# POWR0001_BCR_LT1513.net
KiCad netlist of a schematic drawn in Altium Designer
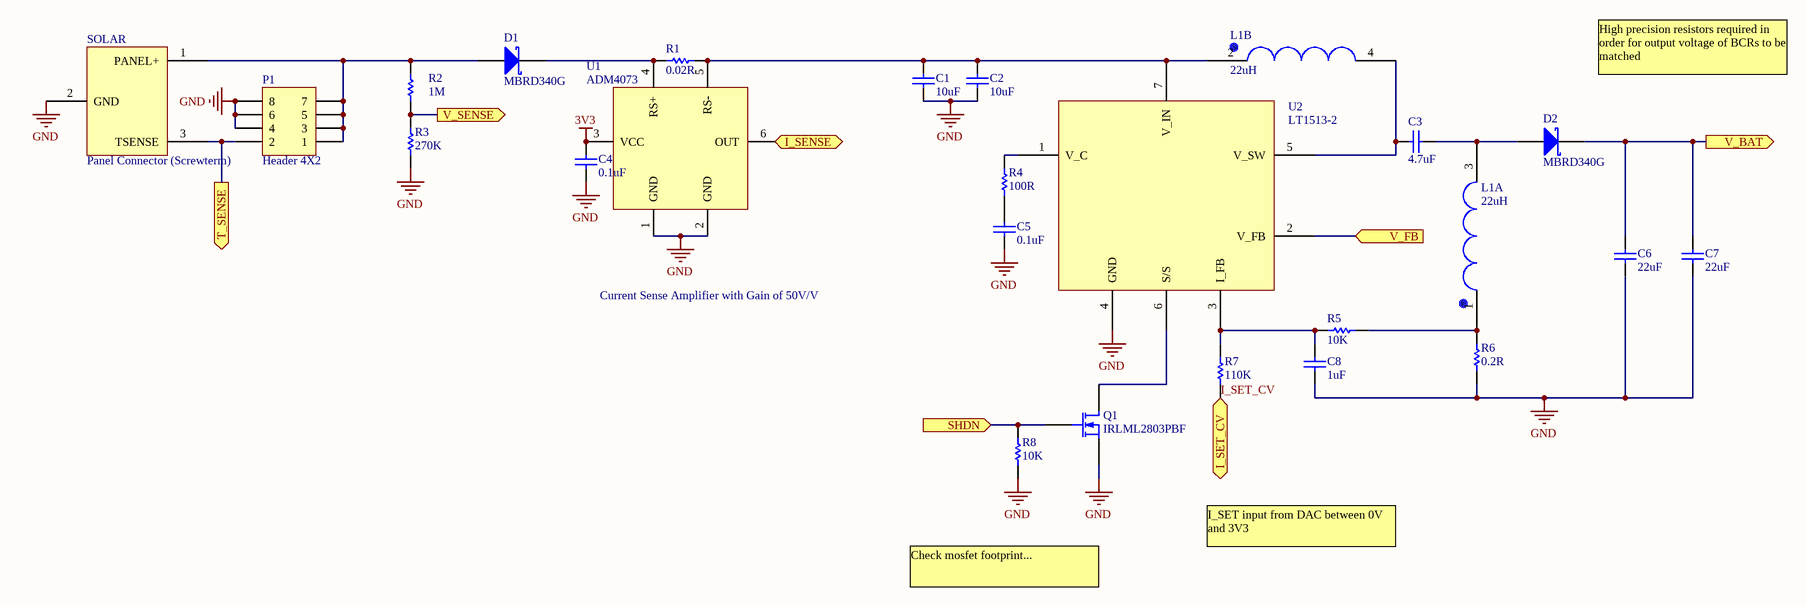
[diagram p0: POWR0001_BCR_LT1513.SchDoc]

(export (version "E")
  (design (tool "Eeschema 10.0.6"))
  (components
    (comp (ref "C1")
      (value "10uF")
      (footprint "CAPC3225M")
      (description "Capacitor")
      (fields (field (name "Comment") "Cap") (field (name "PUBLISHER") "Altium Limited"))
      (libsource (lib "Miscellaneous Devices") (part "Cap"))
    )
    (comp (ref "C2")
      (value "10uF")
      (footprint "CAPC3225M")
      (description "Capacitor")
      (fields (field (name "Comment") "Cap") (field (name "PUBLISHER") "Altium Limited"))
      (libsource (lib "Miscellaneous Devices") (part "Cap"))
    )
    (comp (ref "C3")
      (value "4.7uF")
      (footprint "CAPC3225M")
      (description "Capacitor")
      (fields (field (name "Comment") "Cap") (field (name "PUBLISHER") "Altium Limited"))
      (libsource (lib "Miscellaneous Devices") (part "Cap"))
    )
    (comp (ref "C4")
      (value "0.1uF")
      (footprint "CAPC2012M")
      (description "Capacitor")
      (fields (field (name "Comment") "Cap") (field (name "PUBLISHER") "Altium Limited"))
      (libsource (lib "Miscellaneous Devices") (part "Cap"))
    )
    (comp (ref "C5")
      (value "0.1uF")
      (footprint "CAPC2012M")
      (description "Capacitor")
      (fields (field (name "Comment") "Cap") (field (name "PUBLISHER") "Altium Limited"))
      (libsource (lib "Miscellaneous Devices") (part "Cap"))
    )
    (comp (ref "C6")
      (value "22uF")
      (footprint "CAPC4532M")
      (description "Capacitor")
      (fields (field (name "Comment") "Cap") (field (name "PUBLISHER") "Altium Limited"))
      (libsource (lib "Miscellaneous Devices") (part "Cap"))
    )
    (comp (ref "C7")
      (value "22uF")
      (footprint "CAPC4532M")
      (description "Capacitor")
      (fields (field (name "Comment") "Cap") (field (name "PUBLISHER") "Altium Limited"))
      (libsource (lib "Miscellaneous Devices") (part "Cap"))
    )
    (comp (ref "C8")
      (value "1uF")
      (footprint "CAPC2012M")
      (description "Capacitor")
      (fields (field (name "Comment") "Cap") (field (name "PUBLISHER") "Altium Limited"))
      (libsource (lib "Miscellaneous Devices") (part "Cap"))
    )
    (comp (ref "D1")
      (value "MBRD340G")
      (footprint "TO229P990X238-3N")
      (description "Schottky Rectifier")
      (fields (field (name "PUBLISHER") "Altium Limited"))
      (libsource (lib "Miscellaneous Devices") (part "Diode 11DQ03"))
    )
    (comp (ref "D2")
      (value "MBRD340G")
      (footprint "TO229P990X238-3N")
      (description "Schottky Rectifier")
      (fields (field (name "PUBLISHER") "Altium Limited"))
      (libsource (lib "Miscellaneous Devices") (part "Diode 11DQ03"))
    )
    (comp (ref "L1")
      (value "22uH")
      (footprint "DRQ125")
      (fields (field (name "Comment") "DRQ125 Dual Inductor"))
      (libsource (lib "LT1513") (part "DRQ125 Dual Inductor"))
    )
    (comp (ref "P1")
      (value "Header 4X2")
      (footprint "HDR2X4")
      (description "Header, 4-Pin, Dual row")
      (fields (field (name "PUBLISHER") "Altium Limited"))
      (libsource (lib "Miscellaneous Connectors") (part "Header 4X2"))
    )
    (comp (ref "Q1")
      (value "IRLML2803PBF")
      (footprint "SOT-23_N")
      (description "N-Channel MOSFET")
      (fields (field (name "PUBLISHER") "Altium Limited"))
      (libsource (lib "Miscellaneous Devices") (part "MOSFET-N"))
    )
    (comp (ref "R1")
      (value "0.02R")
      (footprint "RESC2012M")
      (description "Resistor")
      (fields (field (name "Comment") "Res1") (field (name "PUBLISHER") "Altium Limited"))
      (libsource (lib "Miscellaneous Devices") (part "Res1"))
    )
    (comp (ref "R2")
      (value "1M")
      (footprint "RESC2012M")
      (description "Resistor")
      (fields (field (name "Comment") "Res1") (field (name "PUBLISHER") "Altium Limited"))
      (libsource (lib "Miscellaneous Devices") (part "Res1"))
    )
    (comp (ref "R3")
      (value "270K")
      (footprint "RESC2012M")
      (description "Resistor")
      (fields (field (name "Comment") "Res1") (field (name "PUBLISHER") "Altium Limited"))
      (libsource (lib "Miscellaneous Devices") (part "Res1"))
    )
    (comp (ref "R4")
      (value "100R")
      (footprint "RESC2012M")
      (description "Resistor")
      (fields (field (name "Comment") "Res1") (field (name "PUBLISHER") "Altium Limited"))
      (libsource (lib "Miscellaneous Devices") (part "Res1"))
    )
    (comp (ref "R5")
      (value "10K")
      (footprint "RESC2012M")
      (description "Resistor")
      (fields (field (name "Comment") "Res1") (field (name "PUBLISHER") "Altium Limited"))
      (libsource (lib "Miscellaneous Devices") (part "Res1"))
    )
    (comp (ref "R6")
      (value "0.2R")
      (footprint "RESC2012M")
      (description "Resistor")
      (fields (field (name "Comment") "Res1") (field (name "PUBLISHER") "Altium Limited"))
      (libsource (lib "Miscellaneous Devices") (part "Res1"))
    )
    (comp (ref "R7")
      (value "110K")
      (footprint "RESC2012M")
      (description "Resistor")
      (fields (field (name "Comment") "Res1") (field (name "PUBLISHER") "Altium Limited"))
      (libsource (lib "Miscellaneous Devices") (part "Res1"))
    )
    (comp (ref "R8")
      (value "10K")
      (footprint "RESC2012M")
      (description "Resistor")
      (fields (field (name "Comment") "Res1") (field (name "PUBLISHER") "Altium Limited"))
      (libsource (lib "Miscellaneous Devices") (part "Res1"))
    )
    (comp (ref "SOLAR")
      (value "Panel Connector (Screwterm)")
      (footprint "5.05mm Terminal Block - 3")
      (libsource (lib "POWR0001_BCR_LT1513") (part "Solar Panel Connector"))
    )
    (comp (ref "U1")
      (value "ADM4073")
      (footprint "SOT95P285X145-6N")
      (description "Current Sense Amplifer")
      (libsource (lib "Schlib1") (part "ADM4073"))
    )
    (comp (ref "U2")
      (value "LT1513-2")
      (footprint "TO152P1396X238-8N")
      (libsource (lib "LT1513") (part "LT1513"))
    )
  )
  (nets
    (net (code "1") (name "/I_SENSE") (class "Default")
      (node (ref "U1") (pin "6") (pinfunction "OUT_6") (pintype "passive"))
    )
    (net (code "2") (name "/I_SET_CV") (class "Default")
      (node (ref "R7") (pin "2") (pinfunction "2_2") (pintype "passive"))
    )
    (net (code "3") (name "/SHDN") (class "Default")
      (node (ref "Q1") (pin "2") (pinfunction "G_2") (pintype "passive"))
      (node (ref "R8") (pin "1") (pinfunction "1_1") (pintype "passive"))
    )
    (net (code "4") (name "/T_SENSE") (class "Default")
      (node (ref "P1") (pin "2") (pinfunction "2_2") (pintype "passive"))
      (node (ref "SOLAR") (pin "3") (pinfunction "TSENSE_3") (pintype "passive"))
    )
    (net (code "5") (name "/V_BAT") (class "Default")
      (node (ref "C6") (pin "1") (pinfunction "1_1") (pintype "passive"))
      (node (ref "C7") (pin "1") (pinfunction "1_1") (pintype "passive"))
      (node (ref "D2") (pin "2") (pinfunction "K_2") (pintype "passive"))
    )
    (net (code "6") (name "/V_FB") (class "Default")
      (node (ref "U2") (pin "2") (pinfunction "V_FB_2") (pintype "passive"))
    )
    (net (code "7") (name "/V_SENSE") (class "Default")
      (node (ref "R2") (pin "2") (pinfunction "2_2") (pintype "passive"))
      (node (ref "R3") (pin "1") (pinfunction "1_1") (pintype "passive"))
    )
    (net (code "8") (name "3V3") (class "Default")
      (node (ref "C4") (pin "1") (pinfunction "1_1") (pintype "passive"))
      (node (ref "U1") (pin "3") (pinfunction "VCC_3") (pintype "passive"))
    )
    (net (code "9") (name "GND") (class "Default")
      (node (ref "C1") (pin "2") (pinfunction "2_2") (pintype "passive"))
      (node (ref "C2") (pin "2") (pinfunction "2_2") (pintype "passive"))
      (node (ref "C4") (pin "2") (pinfunction "2_2") (pintype "passive"))
      (node (ref "C5") (pin "2") (pinfunction "2_2") (pintype "passive"))
      (node (ref "C6") (pin "2") (pinfunction "2_2") (pintype "passive"))
      (node (ref "C7") (pin "2") (pinfunction "2_2") (pintype "passive"))
      (node (ref "C8") (pin "1") (pinfunction "1_1") (pintype "passive"))
      (node (ref "P1") (pin "4") (pinfunction "4_4") (pintype "passive"))
      (node (ref "P1") (pin "6") (pinfunction "6_6") (pintype "passive"))
      (node (ref "P1") (pin "8") (pinfunction "8_8") (pintype "passive"))
      (node (ref "Q1") (pin "3") (pinfunction "S_3") (pintype "passive"))
      (node (ref "R3") (pin "2") (pinfunction "2_2") (pintype "passive"))
      (node (ref "R6") (pin "1") (pinfunction "1_1") (pintype "passive"))
      (node (ref "R8") (pin "2") (pinfunction "2_2") (pintype "passive"))
      (node (ref "SOLAR") (pin "2") (pinfunction "GND_2") (pintype "passive"))
      (node (ref "U1") (pin "1") (pinfunction "GND_1") (pintype "passive"))
      (node (ref "U1") (pin "2") (pinfunction "GND_2") (pintype "passive"))
      (node (ref "U2") (pin "4") (pinfunction "GND_4") (pintype "passive"))
    )
    (net (code "10") (name "Net-(C5-Pad1)") (class "Default")
      (node (ref "C5") (pin "1") (pinfunction "1_1") (pintype "passive"))
      (node (ref "R4") (pin "2") (pinfunction "2_2") (pintype "passive"))
    )
    (net (code "11") (name "Net-(D1-A)") (class "Default")
      (node (ref "D1") (pin "1") (pinfunction "A_1") (pintype "passive"))
      (node (ref "P1") (pin "1") (pinfunction "1_1") (pintype "passive"))
      (node (ref "P1") (pin "3") (pinfunction "3_3") (pintype "passive"))
      (node (ref "P1") (pin "5") (pinfunction "5_5") (pintype "passive"))
      (node (ref "P1") (pin "7") (pinfunction "7_7") (pintype "passive"))
      (node (ref "R2") (pin "1") (pinfunction "1_1") (pintype "passive"))
      (node (ref "SOLAR") (pin "1") (pinfunction "PANEL+_1") (pintype "passive"))
    )
    (net (code "12") (name "Net-(D1-K)") (class "Default")
      (node (ref "D1") (pin "2") (pinfunction "K_2") (pintype "passive"))
      (node (ref "R1") (pin "2") (pinfunction "2_2") (pintype "passive"))
      (node (ref "U1") (pin "4") (pinfunction "RS+_4") (pintype "passive"))
    )
    (net (code "13") (name "Net-(D2-A)") (class "Default")
      (node (ref "C3") (pin "1") (pinfunction "1_1") (pintype "passive"))
      (node (ref "D2") (pin "1") (pinfunction "A_1") (pintype "passive"))
      (node (ref "L1") (pin "3") (pinfunction "18_3") (pintype "passive"))
    )
    (net (code "14") (name "Net-(L1A-17)") (class "Default")
      (node (ref "L1") (pin "1") (pinfunction "17_1") (pintype "passive"))
      (node (ref "R5") (pin "1") (pinfunction "1_1") (pintype "passive"))
      (node (ref "R6") (pin "2") (pinfunction "2_2") (pintype "passive"))
    )
    (net (code "15") (name "Net-(L1B-17)") (class "Default")
      (node (ref "C1") (pin "1") (pinfunction "1_1") (pintype "passive"))
      (node (ref "C2") (pin "1") (pinfunction "1_1") (pintype "passive"))
      (node (ref "L1") (pin "2") (pinfunction "17_2") (pintype "passive"))
      (node (ref "R1") (pin "1") (pinfunction "1_1") (pintype "passive"))
      (node (ref "U1") (pin "5") (pinfunction "RS-_5") (pintype "passive"))
      (node (ref "U2") (pin "7") (pinfunction "V_IN_7") (pintype "passive"))
    )
    (net (code "16") (name "Net-(L1B-18)") (class "Default")
      (node (ref "C3") (pin "2") (pinfunction "2_2") (pintype "passive"))
      (node (ref "L1") (pin "4") (pinfunction "18_4") (pintype "passive"))
      (node (ref "U2") (pin "5") (pinfunction "V_SW_5") (pintype "passive"))
    )
    (net (code "17") (name "Net-(Q1-D)") (class "Default")
      (node (ref "Q1") (pin "1") (pinfunction "D_1") (pintype "passive"))
      (node (ref "U2") (pin "6") (pinfunction "S/S_6") (pintype "passive"))
    )
    (net (code "18") (name "Net-(U2-I_FB)") (class "Default")
      (node (ref "C8") (pin "2") (pinfunction "2_2") (pintype "passive"))
      (node (ref "R5") (pin "2") (pinfunction "2_2") (pintype "passive"))
      (node (ref "R7") (pin "1") (pinfunction "1_1") (pintype "passive"))
      (node (ref "U2") (pin "3") (pinfunction "I_FB_3") (pintype "passive"))
    )
    (net (code "19") (name "Net-(U2-V_C)") (class "Default")
      (node (ref "R4") (pin "1") (pinfunction "1_1") (pintype "passive"))
      (node (ref "U2") (pin "1") (pinfunction "V_C_1") (pintype "passive"))
    )
  )
)
